# nodemcu_board.net
KiCad netlist of a schematic drawn in EAGLE
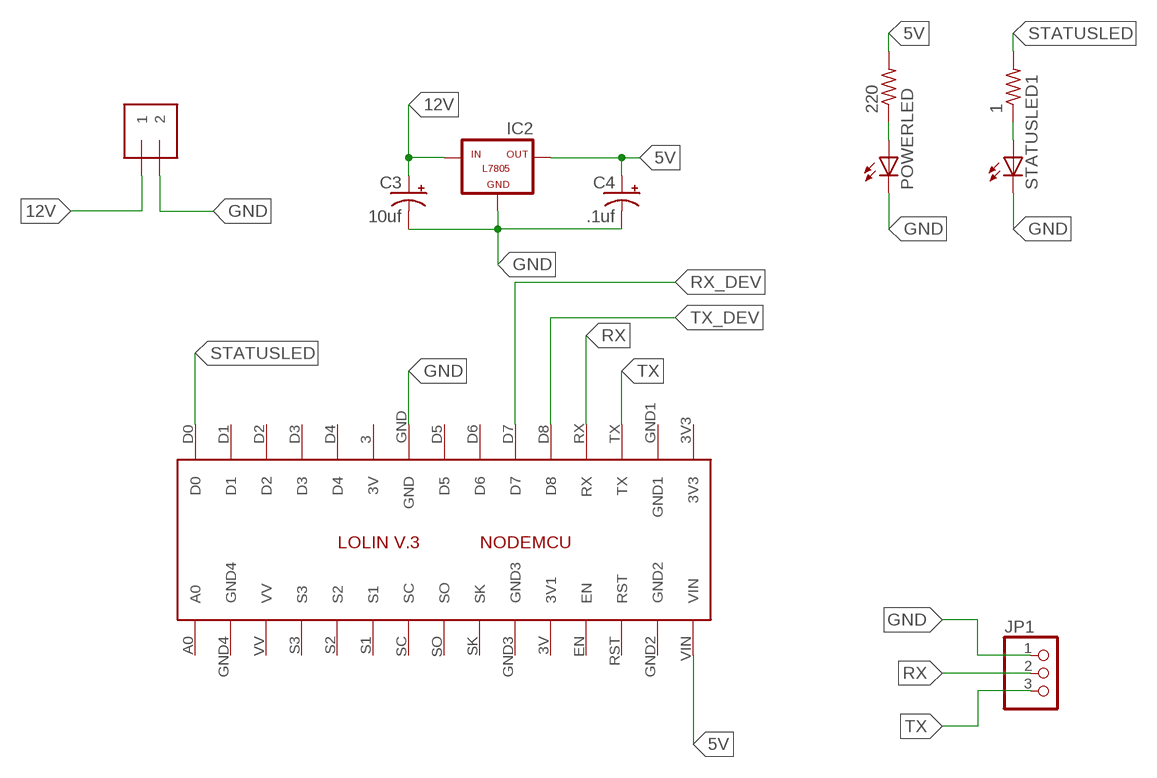
[diagram p0: schematic, sheet 1]

(export (version "E")
  (design (tool "Eeschema 10.0.6"))
  (components
    (comp (ref "1")
      (value "R-US_0204/5")
      (footprint "eagle-import:0204_5")
      (libsource (lib "eagle-import") (part "R-US_0204/5"))
    )
    (comp (ref "220")
      (value "R-US_0204/5")
      (footprint "eagle-import:0204_5")
      (libsource (lib "eagle-import") (part "R-US_0204/5"))
    )
    (comp (ref "C3")
      (value "10uf")
      (footprint "eagle-import:E5-5")
      (libsource (lib "eagle-import") (part "CPOL-USE5-5"))
    )
    (comp (ref "C4")
      (value ".1uf")
      (footprint "eagle-import:E5-5")
      (libsource (lib "eagle-import") (part "CPOL-USE5-5"))
    )
    (comp (ref "IC1")
      (value "NODEMCU_LOLINV3")
      (footprint "eagle-import:NODEMCU_LOLINV3")
      (libsource (lib "eagle-import") (part "NODEMCU_LOLINV3"))
    )
    (comp (ref "IC2")
      (value "L7805")
      (footprint "eagle-import:78XXL")
      (libsource (lib "eagle-import") (part "L7805"))
    )
    (comp (ref "J1")
      (value "1X2-3.5MM")
      (footprint "eagle-import:1X2-3.5MM")
      (libsource (lib "eagle-import") (part "1X2-3.5MM"))
    )
    (comp (ref "JP1")
      (value "PINHD-1X3")
      (footprint "eagle-import:1X03")
      (libsource (lib "eagle-import") (part "PINHD-1X3"))
    )
    (comp (ref "POWERLED")
      (value "LED5MM")
      (footprint "eagle-import:LED5MM")
      (libsource (lib "eagle-import") (part "LED5MM"))
    )
    (comp (ref "STATUSLED1")
      (value "LED5MM")
      (footprint "eagle-import:LED5MM")
      (libsource (lib "eagle-import") (part "LED5MM"))
    )
  )
  (nets
    (net (code "1") (name "5V") (class "Default")
      (node (ref "220") (pin "2") (pinfunction "2_2") (pintype "passive"))
      (node (ref "C4") (pin "+") (pinfunction "+_+") (pintype "passive"))
      (node (ref "IC1") (pin "VIN") (pinfunction "VIN_VIN") (pintype "bidirectional"))
      (node (ref "IC2") (pin "OUT") (pinfunction "OUT_OUT") (pintype "passive"))
    )
    (net (code "2") (name "12V") (class "Default")
      (node (ref "C3") (pin "+") (pinfunction "+_+") (pintype "passive"))
      (node (ref "IC2") (pin "IN") (pinfunction "IN_IN") (pintype "input"))
      (node (ref "J1") (pin "1") (pinfunction "1_1") (pintype "passive"))
    )
    (net (code "3") (name "GND") (class "Default")
      (node (ref "C3") (pin "-") (pinfunction "-_-") (pintype "passive"))
      (node (ref "C4") (pin "-") (pinfunction "-_-") (pintype "passive"))
      (node (ref "IC1") (pin "GND") (pinfunction "GND_GND") (pintype "bidirectional"))
      (node (ref "IC2") (pin "GND") (pinfunction "GND_GND") (pintype "input"))
      (node (ref "J1") (pin "2") (pinfunction "2_2") (pintype "passive"))
      (node (ref "JP1") (pin "1") (pinfunction "1_1") (pintype "passive"))
      (node (ref "POWERLED") (pin "K") (pinfunction "C_K") (pintype "passive"))
      (node (ref "STATUSLED1") (pin "K") (pinfunction "C_K") (pintype "passive"))
    )
    (net (code "4") (name "Net-(1-Pad1)") (class "Default")
      (node (ref "1") (pin "1") (pinfunction "1_1") (pintype "passive"))
      (node (ref "STATUSLED1") (pin "A") (pinfunction "A_A") (pintype "passive"))
    )
    (net (code "5") (name "Net-(220-Pad1)") (class "Default")
      (node (ref "220") (pin "1") (pinfunction "1_1") (pintype "passive"))
      (node (ref "POWERLED") (pin "A") (pinfunction "A_A") (pintype "passive"))
    )
    (net (code "6") (name "RX") (class "Default")
      (node (ref "IC1") (pin "RX") (pinfunction "RX_RX") (pintype "bidirectional"))
      (node (ref "JP1") (pin "2") (pinfunction "2_2") (pintype "passive"))
    )
    (net (code "7") (name "RX_DEV") (class "Default")
      (node (ref "IC1") (pin "D7") (pinfunction "D7_D7") (pintype "bidirectional"))
    )
    (net (code "8") (name "STATUSLED") (class "Default")
      (node (ref "1") (pin "2") (pinfunction "2_2") (pintype "passive"))
      (node (ref "IC1") (pin "D0") (pinfunction "D0_D0") (pintype "bidirectional"))
    )
    (net (code "9") (name "TX") (class "Default")
      (node (ref "IC1") (pin "TX") (pinfunction "TX_TX") (pintype "bidirectional"))
      (node (ref "JP1") (pin "3") (pinfunction "3_3") (pintype "passive"))
    )
    (net (code "10") (name "TX_DEV") (class "Default")
      (node (ref "IC1") (pin "D8") (pinfunction "D8_D8") (pintype "bidirectional"))
    )
    (net (code "11") (name "unconnected-(IC1-3V-Pad3)") (class "Default")
      (node (ref "IC1") (pin "3") (pinfunction "3V_3") (pintype "bidirectional"))
    )
    (net (code "12") (name "unconnected-(IC1-3V1-Pad3V)") (class "Default")
      (node (ref "IC1") (pin "3V") (pinfunction "3V1_3V") (pintype "bidirectional"))
    )
    (net (code "13") (name "unconnected-(IC1-Pad3V3)") (class "Default")
      (node (ref "IC1") (pin "3V3") (pinfunction "3V3_3V3") (pintype "bidirectional"))
    )
    (net (code "14") (name "unconnected-(IC1-PadA0)") (class "Default")
      (node (ref "IC1") (pin "A0") (pinfunction "A0_A0") (pintype "bidirectional"))
    )
    (net (code "15") (name "unconnected-(IC1-PadD1)") (class "Default")
      (node (ref "IC1") (pin "D1") (pinfunction "D1_D1") (pintype "bidirectional"))
    )
    (net (code "16") (name "unconnected-(IC1-PadD2)") (class "Default")
      (node (ref "IC1") (pin "D2") (pinfunction "D2_D2") (pintype "bidirectional"))
    )
    (net (code "17") (name "unconnected-(IC1-PadD3)") (class "Default")
      (node (ref "IC1") (pin "D3") (pinfunction "D3_D3") (pintype "bidirectional"))
    )
    (net (code "18") (name "unconnected-(IC1-PadD4)") (class "Default")
      (node (ref "IC1") (pin "D4") (pinfunction "D4_D4") (pintype "bidirectional"))
    )
    (net (code "19") (name "unconnected-(IC1-PadD5)") (class "Default")
      (node (ref "IC1") (pin "D5") (pinfunction "D5_D5") (pintype "bidirectional"))
    )
    (net (code "20") (name "unconnected-(IC1-PadD6)") (class "Default")
      (node (ref "IC1") (pin "D6") (pinfunction "D6_D6") (pintype "bidirectional"))
    )
    (net (code "21") (name "unconnected-(IC1-PadEN)") (class "Default")
      (node (ref "IC1") (pin "EN") (pinfunction "EN_EN") (pintype "bidirectional"))
    )
    (net (code "22") (name "unconnected-(IC1-PadGND1)") (class "Default")
      (node (ref "IC1") (pin "GND1") (pinfunction "GND1_GND1") (pintype "bidirectional"))
    )
    (net (code "23") (name "unconnected-(IC1-PadGND2)") (class "Default")
      (node (ref "IC1") (pin "GND2") (pinfunction "GND2_GND2") (pintype "bidirectional"))
    )
    (net (code "24") (name "unconnected-(IC1-PadGND3)") (class "Default")
      (node (ref "IC1") (pin "GND3") (pinfunction "GND3_GND3") (pintype "bidirectional"))
    )
    (net (code "25") (name "unconnected-(IC1-PadGND4)") (class "Default")
      (node (ref "IC1") (pin "GND4") (pinfunction "GND4_GND4") (pintype "bidirectional"))
    )
    (net (code "26") (name "unconnected-(IC1-PadRST)") (class "Default")
      (node (ref "IC1") (pin "RST") (pinfunction "RST_RST") (pintype "bidirectional"))
    )
    (net (code "27") (name "unconnected-(IC1-PadS1)") (class "Default")
      (node (ref "IC1") (pin "S1") (pinfunction "S1_S1") (pintype "bidirectional"))
    )
    (net (code "28") (name "unconnected-(IC1-PadS2)") (class "Default")
      (node (ref "IC1") (pin "S2") (pinfunction "S2_S2") (pintype "bidirectional"))
    )
    (net (code "29") (name "unconnected-(IC1-PadS3)") (class "Default")
      (node (ref "IC1") (pin "S3") (pinfunction "S3_S3") (pintype "bidirectional"))
    )
    (net (code "30") (name "unconnected-(IC1-PadSC)") (class "Default")
      (node (ref "IC1") (pin "SC") (pinfunction "SC_SC") (pintype "bidirectional"))
    )
    (net (code "31") (name "unconnected-(IC1-PadSK)") (class "Default")
      (node (ref "IC1") (pin "SK") (pinfunction "SK_SK") (pintype "bidirectional"))
    )
    (net (code "32") (name "unconnected-(IC1-PadSO)") (class "Default")
      (node (ref "IC1") (pin "SO") (pinfunction "SO_SO") (pintype "bidirectional"))
    )
    (net (code "33") (name "unconnected-(IC1-PadVV)") (class "Default")
      (node (ref "IC1") (pin "VV") (pinfunction "VV_VV") (pintype "bidirectional"))
    )
  )
)
